# 600W_INV_MCU-2.net
KiCad netlist of a schematic drawn in Altium Designer
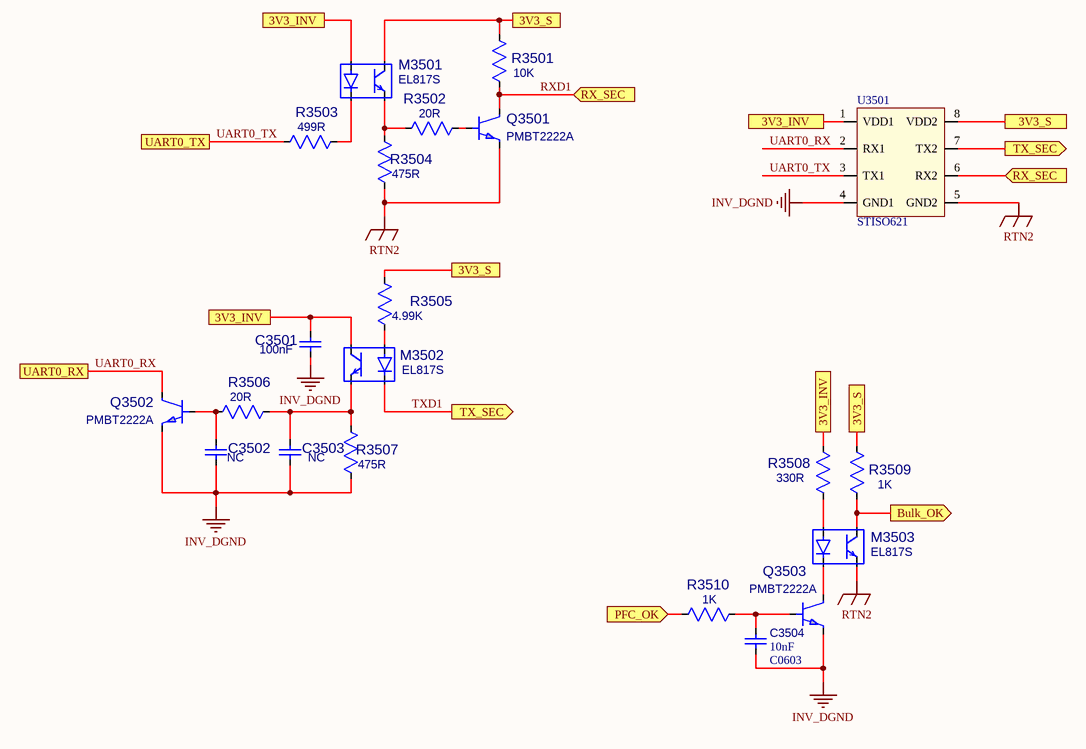
[diagram p0: 600W INV MCU-2.SchDoc]

(export (version "E")
  (design (tool "Eeschema 10.0.6"))
  (components
    (comp (ref "C3501")
      (value "100nF")
      (footprint "C0603L")
      (description "C0603")
      (libsource (lib "SMD-R") (part "C0603"))
    )
    (comp (ref "C3502")
      (value "NC")
      (footprint "C0603L")
      (description "C0603")
      (libsource (lib "SMD-R") (part "C0603"))
    )
    (comp (ref "C3503")
      (value "NC")
      (footprint "C0603L")
      (description "C0603")
      (libsource (lib "SMD-R") (part "C0603"))
    )
    (comp (ref "C3504")
      (value "10nF")
      (footprint "C0603L")
      (description "C0603")
      (fields (field (name "PACKAGE") "C0603"))
      (libsource (lib "SMD-R") (part "C0603"))
    )
    (comp (ref "M3501")
      (value "EL817S")
      (footprint "PHOTO-PS2561DLA")
      (description "PHOTO-PS2561DLA")
      (libsource (lib "") (part "PHOTO-PS2561DLA_1"))
    )
    (comp (ref "M3502")
      (value "EL817S")
      (footprint "PHOTO-PS2561DLA")
      (description "PHOTO-PS2561DLA")
      (libsource (lib "SMD-R") (part "PHOTO-PS2561DLA"))
    )
    (comp (ref "M3503")
      (value "EL817S")
      (footprint "PHOTO-PS2561DLA")
      (description "PHOTO-PS2561DLA")
      (libsource (lib "") (part "PHOTO-PS2561DLA_1"))
    )
    (comp (ref "Q3501")
      (value "PMBT2222A")
      (footprint "SOT23-CBE")
      (description "SOT-23-NPN")
      (libsource (lib "SMD-R") (part "NPN"))
    )
    (comp (ref "Q3502")
      (value "PMBT2222A")
      (footprint "SOT23-CBE")
      (description "SOT-23-NPN")
      (libsource (lib "SMD-R") (part "NPN"))
    )
    (comp (ref "Q3503")
      (value "PMBT2222A")
      (footprint "SOT23-CBE")
      (description "SOT-23-NPN")
      (libsource (lib "SMD-R") (part "NPN"))
    )
    (comp (ref "R3501")
      (value "10K")
      (footprint "R0603L")
      (description "R0603")
      (libsource (lib "SMD-R") (part "R0603"))
    )
    (comp (ref "R3502")
      (value "20R")
      (footprint "R0603L")
      (description "R0603")
      (libsource (lib "SMD-R") (part "R0603"))
    )
    (comp (ref "R3503")
      (value "499R")
      (footprint "R0603L")
      (description "R0603")
      (libsource (lib "SMD-R") (part "R0603"))
    )
    (comp (ref "R3504")
      (value "475R")
      (footprint "R0603L")
      (description "R0603")
      (libsource (lib "SMD-R") (part "R0603"))
    )
    (comp (ref "R3505")
      (value "4.99K")
      (footprint "R0603L")
      (description "R0603")
      (libsource (lib "SMD-R") (part "R0603"))
    )
    (comp (ref "R3506")
      (value "20R")
      (footprint "R0603L")
      (description "R0603")
      (libsource (lib "SMD-R") (part "R0603"))
    )
    (comp (ref "R3507")
      (value "475R")
      (footprint "R0603L")
      (description "R0603")
      (libsource (lib "SMD-R") (part "R0603"))
    )
    (comp (ref "R3508")
      (value "330R")
      (footprint "R0603L")
      (description "R0603")
      (libsource (lib "SMD-R") (part "R0603"))
    )
    (comp (ref "R3509")
      (value "1K")
      (footprint "R0603L")
      (description "R0603")
      (libsource (lib "SMD-R") (part "R0603"))
    )
    (comp (ref "R3510")
      (value "1K")
      (footprint "R0603L")
      (description "R0603")
      (libsource (lib "SMD-R") (part "R0603"))
    )
    (comp (ref "U3501")
      (value "STISO621")
      (footprint "SO8")
      (description "LM358")
      (libsource (lib "SMD-R") (part "STISO621"))
    )
  )
  (nets
    (net (code "1") (name "/3V3_INV") (class "Default")
      (node (ref "C3501") (pin "1") (pinfunction "1_1") (pintype "passive"))
      (node (ref "M3501") (pin "1") (pinfunction "1_1") (pintype "passive"))
      (node (ref "M3502") (pin "4") (pinfunction "4_4") (pintype "passive"))
      (node (ref "R3508") (pin "2") (pinfunction "1_2") (pintype "passive"))
      (node (ref "U3501") (pin "1") (pinfunction "VDD1_1") (pintype "passive"))
    )
    (net (code "2") (name "/3V3_S") (class "Default")
      (node (ref "M3501") (pin "4") (pinfunction "4_4") (pintype "passive"))
      (node (ref "R3501") (pin "2") (pinfunction "1_2") (pintype "passive"))
      (node (ref "R3505") (pin "2") (pinfunction "1_2") (pintype "passive"))
      (node (ref "R3509") (pin "2") (pinfunction "1_2") (pintype "passive"))
      (node (ref "U3501") (pin "8") (pinfunction "VDD2_8") (pintype "passive"))
    )
    (net (code "3") (name "/Bulk_OK") (class "Default")
      (node (ref "M3503") (pin "4") (pinfunction "4_4") (pintype "passive"))
      (node (ref "R3509") (pin "1") (pinfunction "1_1") (pintype "passive"))
    )
    (net (code "4") (name "/PFC_OK") (class "Default")
      (node (ref "R3510") (pin "2") (pinfunction "1_2") (pintype "passive"))
    )
    (net (code "5") (name "/RXD1") (class "Default")
      (node (ref "Q3501") (pin "C") (pinfunction "C_C") (pintype "passive"))
      (node (ref "R3501") (pin "1") (pinfunction "1_1") (pintype "passive"))
      (node (ref "U3501") (pin "6") (pinfunction "RX2_6") (pintype "passive"))
    )
    (net (code "6") (name "/TXD1") (class "Default")
      (node (ref "M3502") (pin "2") (pinfunction "2_2") (pintype "passive"))
      (node (ref "U3501") (pin "7") (pinfunction "TX2_7") (pintype "passive"))
    )
    (net (code "7") (name "/UART0_RX") (class "Default")
      (node (ref "Q3502") (pin "C") (pinfunction "C_C") (pintype "passive"))
      (node (ref "U3501") (pin "2") (pinfunction "RX1_2") (pintype "passive"))
    )
    (net (code "8") (name "/UART0_TX") (class "Default")
      (node (ref "R3503") (pin "2") (pinfunction "1_2") (pintype "passive"))
      (node (ref "U3501") (pin "3") (pinfunction "TX1_3") (pintype "passive"))
    )
    (net (code "9") (name "INV_DGND") (class "Default")
      (node (ref "C3501") (pin "2") (pinfunction "2_2") (pintype "passive"))
      (node (ref "C3502") (pin "2") (pinfunction "2_2") (pintype "passive"))
      (node (ref "C3503") (pin "2") (pinfunction "2_2") (pintype "passive"))
      (node (ref "C3504") (pin "1") (pinfunction "1_1") (pintype "passive"))
      (node (ref "Q3502") (pin "E") (pinfunction "E_E") (pintype "passive"))
      (node (ref "Q3503") (pin "E") (pinfunction "E_E") (pintype "passive"))
      (node (ref "R3507") (pin "1") (pinfunction "1_1") (pintype "passive"))
      (node (ref "U3501") (pin "4") (pinfunction "GND1_4") (pintype "passive"))
    )
    (net (code "10") (name "Net-(C3502-Pad1)") (class "Default")
      (node (ref "C3502") (pin "1") (pinfunction "1_1") (pintype "passive"))
      (node (ref "Q3502") (pin "B") (pinfunction "B_B") (pintype "passive"))
      (node (ref "R3506") (pin "2") (pinfunction "1_2") (pintype "passive"))
    )
    (net (code "11") (name "Net-(C3503-Pad1)") (class "Default")
      (node (ref "C3503") (pin "1") (pinfunction "1_1") (pintype "passive"))
      (node (ref "M3502") (pin "3") (pinfunction "3_3") (pintype "passive"))
      (node (ref "R3506") (pin "1") (pinfunction "1_1") (pintype "passive"))
      (node (ref "R3507") (pin "2") (pinfunction "1_2") (pintype "passive"))
    )
    (net (code "12") (name "Net-(C3504-Pad2)") (class "Default")
      (node (ref "C3504") (pin "2") (pinfunction "2_2") (pintype "passive"))
      (node (ref "Q3503") (pin "B") (pinfunction "B_B") (pintype "passive"))
      (node (ref "R3510") (pin "1") (pinfunction "1_1") (pintype "passive"))
    )
    (net (code "13") (name "Net-(M3501-Pad2)") (class "Default")
      (node (ref "M3501") (pin "2") (pinfunction "2_2") (pintype "passive"))
      (node (ref "R3503") (pin "1") (pinfunction "1_1") (pintype "passive"))
    )
    (net (code "14") (name "Net-(M3501-Pad3)") (class "Default")
      (node (ref "M3501") (pin "3") (pinfunction "3_3") (pintype "passive"))
      (node (ref "R3502") (pin "2") (pinfunction "1_2") (pintype "passive"))
      (node (ref "R3504") (pin "2") (pinfunction "1_2") (pintype "passive"))
    )
    (net (code "15") (name "Net-(M3502-Pad1)") (class "Default")
      (node (ref "M3502") (pin "1") (pinfunction "1_1") (pintype "passive"))
      (node (ref "R3505") (pin "1") (pinfunction "1_1") (pintype "passive"))
    )
    (net (code "16") (name "Net-(M3503-Pad1)") (class "Default")
      (node (ref "M3503") (pin "1") (pinfunction "1_1") (pintype "passive"))
      (node (ref "R3508") (pin "1") (pinfunction "1_1") (pintype "passive"))
    )
    (net (code "17") (name "Net-(M3503-Pad2)") (class "Default")
      (node (ref "M3503") (pin "2") (pinfunction "2_2") (pintype "passive"))
      (node (ref "Q3503") (pin "C") (pinfunction "C_C") (pintype "passive"))
    )
    (net (code "18") (name "Net-(Q3501-PadB)") (class "Default")
      (node (ref "Q3501") (pin "B") (pinfunction "B_B") (pintype "passive"))
      (node (ref "R3502") (pin "1") (pinfunction "1_1") (pintype "passive"))
    )
    (net (code "19") (name "RTN2") (class "Default")
      (node (ref "M3503") (pin "3") (pinfunction "3_3") (pintype "passive"))
      (node (ref "Q3501") (pin "E") (pinfunction "E_E") (pintype "passive"))
      (node (ref "R3504") (pin "1") (pinfunction "1_1") (pintype "passive"))
      (node (ref "U3501") (pin "5") (pinfunction "GND2_5") (pintype "passive"))
    )
  )
)
